# Palette_PCB.net
KiCad netlist of a schematic drawn in EAGLE
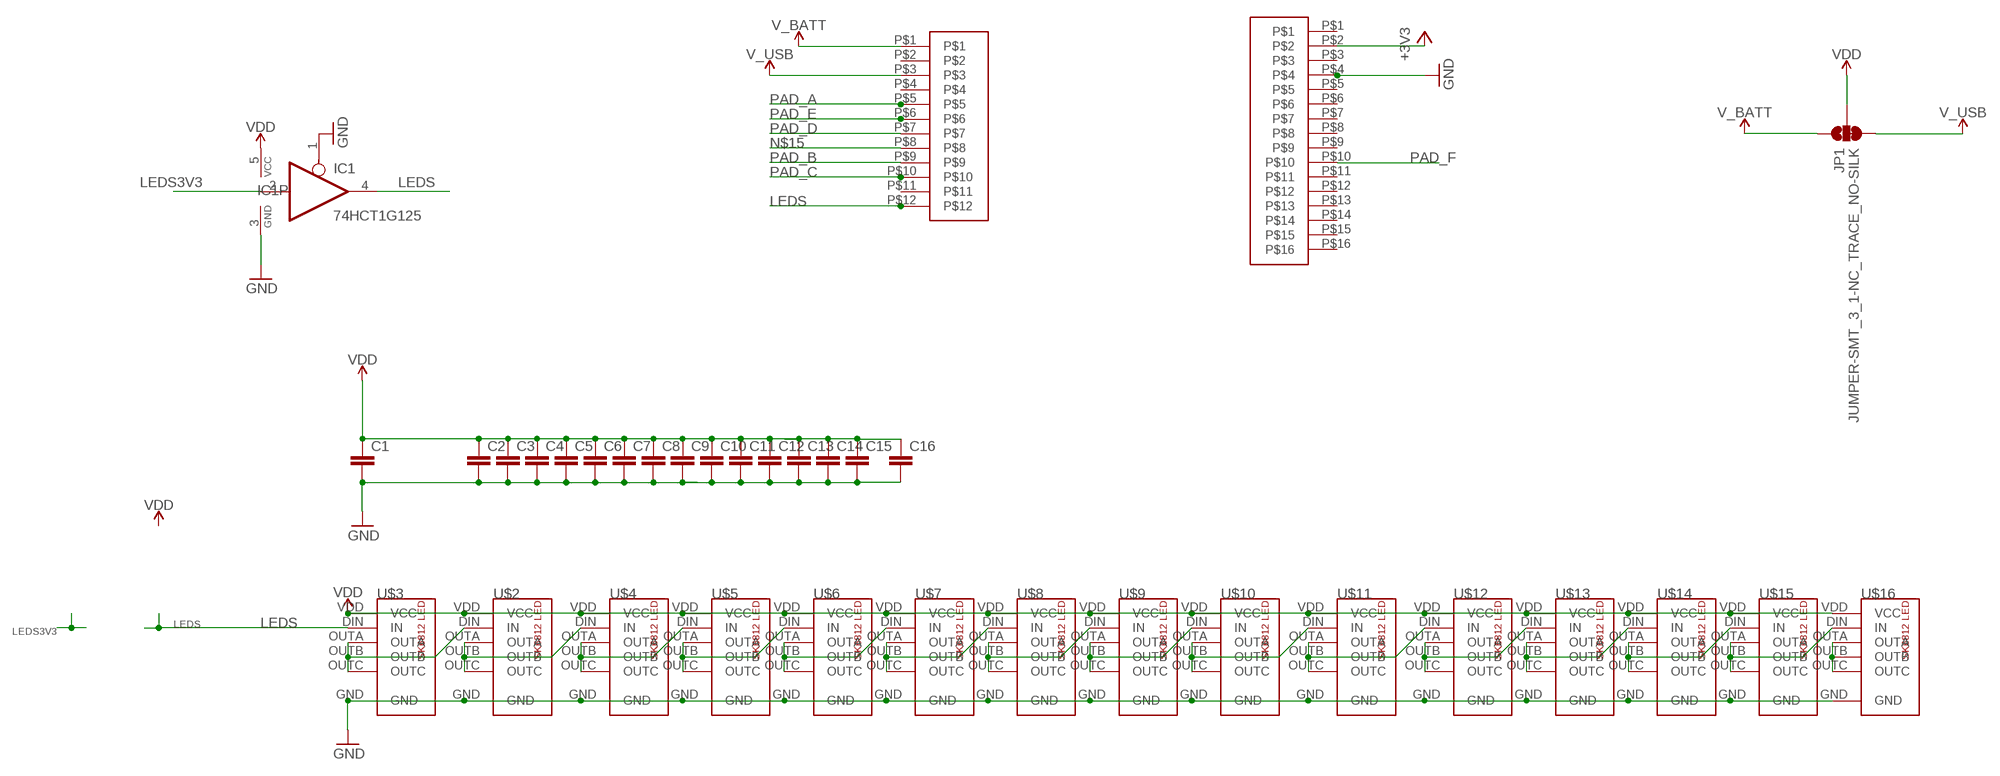
[diagram p0: schematic, sheet 1]

(export (version "E")
  (design (tool "Eeschema 10.0.6"))
  (components
    (comp (ref "C1")
      (value "C-EUC0402K")
      (footprint "eagle-import:C0402K")
      (libsource (lib "eagle-import") (part "C-EUC0402K"))
    )
    (comp (ref "C2")
      (value "C-EUC0402K")
      (footprint "eagle-import:C0402K")
      (libsource (lib "eagle-import") (part "C-EUC0402K"))
    )
    (comp (ref "C3")
      (value "C-EUC0402K")
      (footprint "eagle-import:C0402K")
      (libsource (lib "eagle-import") (part "C-EUC0402K"))
    )
    (comp (ref "C4")
      (value "C-EUC0402K")
      (footprint "eagle-import:C0402K")
      (libsource (lib "eagle-import") (part "C-EUC0402K"))
    )
    (comp (ref "C5")
      (value "C-EUC0402K")
      (footprint "eagle-import:C0402K")
      (libsource (lib "eagle-import") (part "C-EUC0402K"))
    )
    (comp (ref "C6")
      (value "C-EUC0402K")
      (footprint "eagle-import:C0402K")
      (libsource (lib "eagle-import") (part "C-EUC0402K"))
    )
    (comp (ref "C7")
      (value "C-EUC0402K")
      (footprint "eagle-import:C0402K")
      (libsource (lib "eagle-import") (part "C-EUC0402K"))
    )
    (comp (ref "C8")
      (value "C-EUC0402K")
      (footprint "eagle-import:C0402K")
      (libsource (lib "eagle-import") (part "C-EUC0402K"))
    )
    (comp (ref "C9")
      (value "C-EUC0402K")
      (footprint "eagle-import:C0402K")
      (libsource (lib "eagle-import") (part "C-EUC0402K"))
    )
    (comp (ref "C10")
      (value "C-EUC0402K")
      (footprint "eagle-import:C0402K")
      (libsource (lib "eagle-import") (part "C-EUC0402K"))
    )
    (comp (ref "C11")
      (value "C-EUC0402K")
      (footprint "eagle-import:C0402K")
      (libsource (lib "eagle-import") (part "C-EUC0402K"))
    )
    (comp (ref "C12")
      (value "C-EUC0402K")
      (footprint "eagle-import:C0402K")
      (libsource (lib "eagle-import") (part "C-EUC0402K"))
    )
    (comp (ref "C13")
      (value "C-EUC0402K")
      (footprint "eagle-import:C0402K")
      (libsource (lib "eagle-import") (part "C-EUC0402K"))
    )
    (comp (ref "C14")
      (value "C-EUC0402K")
      (footprint "eagle-import:C0402K")
      (libsource (lib "eagle-import") (part "C-EUC0402K"))
    )
    (comp (ref "C15")
      (value "C-EUC0402K")
      (footprint "eagle-import:C0402K")
      (libsource (lib "eagle-import") (part "C-EUC0402K"))
    )
    (comp (ref "C16")
      (value "C-EUC0805K")
      (footprint "eagle-import:C0805K")
      (libsource (lib "eagle-import") (part "C-EUC0805K"))
    )
    (comp (ref "IC1")
      (value "74HCT1G125")
      (footprint "eagle-import:SOT23-5")
      (libsource (lib "eagle-import") (part "741G125DBVAHC"))
    )
    (comp (ref "JP1")
      (value "JUMPER-SMT_3_1-NC_TRACE_NO-SILK")
      (footprint "eagle-import:SMT-JUMPER_3_1-NC_TRACE_NO-SILK")
      (libsource (lib "eagle-import") (part "JUMPER-SMT_3_1-NC_TRACE_NO-SILK"))
    )
    (comp (ref "U$2")
      (value "SK6812OK")
      (footprint "eagle-import:SK6812_V2C")
      (libsource (lib "eagle-import") (part "SK6812OK"))
    )
    (comp (ref "U$3")
      (value "SK6812OK")
      (footprint "eagle-import:SK6812_V2C")
      (libsource (lib "eagle-import") (part "SK6812OK"))
    )
    (comp (ref "U$4")
      (value "SK6812OK")
      (footprint "eagle-import:SK6812_V2C")
      (libsource (lib "eagle-import") (part "SK6812OK"))
    )
    (comp (ref "U$5")
      (value "SK6812OK")
      (footprint "eagle-import:SK6812_V2C")
      (libsource (lib "eagle-import") (part "SK6812OK"))
    )
    (comp (ref "U$6")
      (value "SK6812OK")
      (footprint "eagle-import:SK6812_V2C")
      (libsource (lib "eagle-import") (part "SK6812OK"))
    )
    (comp (ref "U$7")
      (value "SK6812OK")
      (footprint "eagle-import:SK6812_V2C")
      (libsource (lib "eagle-import") (part "SK6812OK"))
    )
    (comp (ref "U$8")
      (value "SK6812OK")
      (footprint "eagle-import:SK6812_V2C")
      (libsource (lib "eagle-import") (part "SK6812OK"))
    )
    (comp (ref "U$9")
      (value "SK6812OK")
      (footprint "eagle-import:SK6812_V2C")
      (libsource (lib "eagle-import") (part "SK6812OK"))
    )
    (comp (ref "U$10")
      (value "SK6812OK")
      (footprint "eagle-import:SK6812_V2C")
      (libsource (lib "eagle-import") (part "SK6812OK"))
    )
    (comp (ref "U$11")
      (value "SK6812OK")
      (footprint "eagle-import:SK6812_V2C")
      (libsource (lib "eagle-import") (part "SK6812OK"))
    )
    (comp (ref "U$12")
      (value "SK6812OK")
      (footprint "eagle-import:SK6812_V2C")
      (libsource (lib "eagle-import") (part "SK6812OK"))
    )
    (comp (ref "U$13")
      (value "SK6812OK")
      (footprint "eagle-import:SK6812_V2C")
      (libsource (lib "eagle-import") (part "SK6812OK"))
    )
    (comp (ref "U$14")
      (value "SK6812OK")
      (footprint "eagle-import:SK6812_V2C")
      (libsource (lib "eagle-import") (part "SK6812OK"))
    )
    (comp (ref "U$15")
      (value "SK6812OK")
      (footprint "eagle-import:SK6812_V2C")
      (libsource (lib "eagle-import") (part "SK6812OK"))
    )
    (comp (ref "U$16")
      (value "SK6812OK")
      (footprint "eagle-import:SK6812_V2C")
      (libsource (lib "eagle-import") (part "SK6812OK"))
    )
    (comp (ref "U$17")
      (value "SMD-FEMALE-HEADER-16")
      (footprint "eagle-import:SMD-FEMALE-HEADER-16")
      (libsource (lib "eagle-import") (part "SMD-FEMALE-HEADER-16"))
    )
    (comp (ref "U$18")
      (value "SMD-FEMALE-HEADER-12")
      (footprint "eagle-import:SMD-FEMALE-HEADER-12")
      (libsource (lib "eagle-import") (part "SMD-FEMALE-HEADER-12"))
    )
  )
  (nets
    (net (code "1") (name "+3V3") (class "Default")
      (node (ref "U$17") (pin "P$2") (pinfunction "P$2_P$2") (pintype "bidirectional"))
    )
    (net (code "2") (name "/N$15") (class "Default")
      (node (ref "U$18") (pin "P$8") (pinfunction "P$8_P$8") (pintype "bidirectional"))
    )
    (net (code "3") (name "/PAD_A") (class "Default")
      (node (ref "U$18") (pin "P$5") (pinfunction "P$5_P$5") (pintype "bidirectional"))
    )
    (net (code "4") (name "/PAD_B") (class "Default")
      (node (ref "U$18") (pin "P$9") (pinfunction "P$9_P$9") (pintype "bidirectional"))
    )
    (net (code "5") (name "/PAD_C") (class "Default")
      (node (ref "U$18") (pin "P$10") (pinfunction "P$10_P$10") (pintype "bidirectional"))
    )
    (net (code "6") (name "/PAD_D") (class "Default")
      (node (ref "U$18") (pin "P$7") (pinfunction "P$7_P$7") (pintype "bidirectional"))
    )
    (net (code "7") (name "/PAD_E") (class "Default")
      (node (ref "U$18") (pin "P$6") (pinfunction "P$6_P$6") (pintype "bidirectional"))
    )
    (net (code "8") (name "/PAD_F") (class "Default")
      (node (ref "U$17") (pin "P$10") (pinfunction "P$10_P$10") (pintype "bidirectional"))
    )
    (net (code "9") (name "GND") (class "Default")
      (node (ref "C1") (pin "2") (pinfunction "2_2") (pintype "passive"))
      (node (ref "C10") (pin "2") (pinfunction "2_2") (pintype "passive"))
      (node (ref "C11") (pin "2") (pinfunction "2_2") (pintype "passive"))
      (node (ref "C12") (pin "2") (pinfunction "2_2") (pintype "passive"))
      (node (ref "C13") (pin "2") (pinfunction "2_2") (pintype "passive"))
      (node (ref "C14") (pin "2") (pinfunction "2_2") (pintype "passive"))
      (node (ref "C15") (pin "2") (pinfunction "2_2") (pintype "passive"))
      (node (ref "C16") (pin "2") (pinfunction "2_2") (pintype "passive"))
      (node (ref "C2") (pin "2") (pinfunction "2_2") (pintype "passive"))
      (node (ref "C3") (pin "2") (pinfunction "2_2") (pintype "passive"))
      (node (ref "C4") (pin "2") (pinfunction "2_2") (pintype "passive"))
      (node (ref "C5") (pin "2") (pinfunction "2_2") (pintype "passive"))
      (node (ref "C6") (pin "2") (pinfunction "2_2") (pintype "passive"))
      (node (ref "C7") (pin "2") (pinfunction "2_2") (pintype "passive"))
      (node (ref "C8") (pin "2") (pinfunction "2_2") (pintype "passive"))
      (node (ref "C9") (pin "2") (pinfunction "2_2") (pintype "passive"))
      (node (ref "IC1") (pin "1") (pinfunction "OE_1") (pintype "input"))
      (node (ref "IC1") (pin "3") (pinfunction "GND_3") (pintype "power_in"))
      (node (ref "U$10") (pin "GND") (pinfunction "GND_GND") (pintype "bidirectional"))
      (node (ref "U$11") (pin "GND") (pinfunction "GND_GND") (pintype "bidirectional"))
      (node (ref "U$12") (pin "GND") (pinfunction "GND_GND") (pintype "bidirectional"))
      (node (ref "U$13") (pin "GND") (pinfunction "GND_GND") (pintype "bidirectional"))
      (node (ref "U$14") (pin "GND") (pinfunction "GND_GND") (pintype "bidirectional"))
      (node (ref "U$15") (pin "GND") (pinfunction "GND_GND") (pintype "bidirectional"))
      (node (ref "U$16") (pin "GND") (pinfunction "GND_GND") (pintype "bidirectional"))
      (node (ref "U$17") (pin "P$4") (pinfunction "P$4_P$4") (pintype "bidirectional"))
      (node (ref "U$2") (pin "GND") (pinfunction "GND_GND") (pintype "bidirectional"))
      (node (ref "U$3") (pin "GND") (pinfunction "GND_GND") (pintype "bidirectional"))
      (node (ref "U$4") (pin "GND") (pinfunction "GND_GND") (pintype "bidirectional"))
      (node (ref "U$5") (pin "GND") (pinfunction "GND_GND") (pintype "bidirectional"))
      (node (ref "U$6") (pin "GND") (pinfunction "GND_GND") (pintype "bidirectional"))
      (node (ref "U$7") (pin "GND") (pinfunction "GND_GND") (pintype "bidirectional"))
      (node (ref "U$8") (pin "GND") (pinfunction "GND_GND") (pintype "bidirectional"))
      (node (ref "U$9") (pin "GND") (pinfunction "GND_GND") (pintype "bidirectional"))
    )
    (net (code "10") (name "LEDS") (class "Default")
      (node (ref "IC1") (pin "4") (pinfunction "O_4") (pintype "tri_state"))
      (node (ref "U$18") (pin "P$12") (pinfunction "P$12_P$12") (pintype "bidirectional"))
      (node (ref "U$3") (pin "DIN") (pinfunction "IN_DIN") (pintype "bidirectional"))
    )
    (net (code "11") (name "LEDS3V3") (class "Default")
      (node (ref "IC1") (pin "2") (pinfunction "I_2") (pintype "input"))
    )
    (net (code "12") (name "Net-(U$2-IN)") (class "Default")
      (node (ref "U$2") (pin "DIN") (pinfunction "IN_DIN") (pintype "bidirectional"))
      (node (ref "U$3") (pin "OUTA") (pinfunction "OUTA_OUTA") (pintype "bidirectional"))
      (node (ref "U$3") (pin "OUTB") (pinfunction "OUTB_OUTB") (pintype "bidirectional"))
      (node (ref "U$3") (pin "OUTC") (pinfunction "OUTC_OUTC") (pintype "bidirectional"))
    )
    (net (code "13") (name "Net-(U$4-IN)") (class "Default")
      (node (ref "U$2") (pin "OUTA") (pinfunction "OUTA_OUTA") (pintype "bidirectional"))
      (node (ref "U$2") (pin "OUTB") (pinfunction "OUTB_OUTB") (pintype "bidirectional"))
      (node (ref "U$2") (pin "OUTC") (pinfunction "OUTC_OUTC") (pintype "bidirectional"))
      (node (ref "U$4") (pin "DIN") (pinfunction "IN_DIN") (pintype "bidirectional"))
    )
    (net (code "14") (name "Net-(U$5-IN)") (class "Default")
      (node (ref "U$4") (pin "OUTA") (pinfunction "OUTA_OUTA") (pintype "bidirectional"))
      (node (ref "U$4") (pin "OUTB") (pinfunction "OUTB_OUTB") (pintype "bidirectional"))
      (node (ref "U$4") (pin "OUTC") (pinfunction "OUTC_OUTC") (pintype "bidirectional"))
      (node (ref "U$5") (pin "DIN") (pinfunction "IN_DIN") (pintype "bidirectional"))
    )
    (net (code "15") (name "Net-(U$6-IN)") (class "Default")
      (node (ref "U$5") (pin "OUTA") (pinfunction "OUTA_OUTA") (pintype "bidirectional"))
      (node (ref "U$5") (pin "OUTB") (pinfunction "OUTB_OUTB") (pintype "bidirectional"))
      (node (ref "U$5") (pin "OUTC") (pinfunction "OUTC_OUTC") (pintype "bidirectional"))
      (node (ref "U$6") (pin "DIN") (pinfunction "IN_DIN") (pintype "bidirectional"))
    )
    (net (code "16") (name "Net-(U$7-IN)") (class "Default")
      (node (ref "U$6") (pin "OUTA") (pinfunction "OUTA_OUTA") (pintype "bidirectional"))
      (node (ref "U$6") (pin "OUTB") (pinfunction "OUTB_OUTB") (pintype "bidirectional"))
      (node (ref "U$6") (pin "OUTC") (pinfunction "OUTC_OUTC") (pintype "bidirectional"))
      (node (ref "U$7") (pin "DIN") (pinfunction "IN_DIN") (pintype "bidirectional"))
    )
    (net (code "17") (name "Net-(U$8-IN)") (class "Default")
      (node (ref "U$7") (pin "OUTA") (pinfunction "OUTA_OUTA") (pintype "bidirectional"))
      (node (ref "U$7") (pin "OUTB") (pinfunction "OUTB_OUTB") (pintype "bidirectional"))
      (node (ref "U$7") (pin "OUTC") (pinfunction "OUTC_OUTC") (pintype "bidirectional"))
      (node (ref "U$8") (pin "DIN") (pinfunction "IN_DIN") (pintype "bidirectional"))
    )
    (net (code "18") (name "Net-(U$9-IN)") (class "Default")
      (node (ref "U$8") (pin "OUTA") (pinfunction "OUTA_OUTA") (pintype "bidirectional"))
      (node (ref "U$8") (pin "OUTB") (pinfunction "OUTB_OUTB") (pintype "bidirectional"))
      (node (ref "U$8") (pin "OUTC") (pinfunction "OUTC_OUTC") (pintype "bidirectional"))
      (node (ref "U$9") (pin "DIN") (pinfunction "IN_DIN") (pintype "bidirectional"))
    )
    (net (code "19") (name "Net-(U$10-IN)") (class "Default")
      (node (ref "U$10") (pin "DIN") (pinfunction "IN_DIN") (pintype "bidirectional"))
      (node (ref "U$9") (pin "OUTA") (pinfunction "OUTA_OUTA") (pintype "bidirectional"))
      (node (ref "U$9") (pin "OUTB") (pinfunction "OUTB_OUTB") (pintype "bidirectional"))
      (node (ref "U$9") (pin "OUTC") (pinfunction "OUTC_OUTC") (pintype "bidirectional"))
    )
    (net (code "20") (name "Net-(U$11-IN)") (class "Default")
      (node (ref "U$10") (pin "OUTA") (pinfunction "OUTA_OUTA") (pintype "bidirectional"))
      (node (ref "U$10") (pin "OUTB") (pinfunction "OUTB_OUTB") (pintype "bidirectional"))
      (node (ref "U$10") (pin "OUTC") (pinfunction "OUTC_OUTC") (pintype "bidirectional"))
      (node (ref "U$11") (pin "DIN") (pinfunction "IN_DIN") (pintype "bidirectional"))
    )
    (net (code "21") (name "Net-(U$12-IN)") (class "Default")
      (node (ref "U$11") (pin "OUTA") (pinfunction "OUTA_OUTA") (pintype "bidirectional"))
      (node (ref "U$11") (pin "OUTB") (pinfunction "OUTB_OUTB") (pintype "bidirectional"))
      (node (ref "U$11") (pin "OUTC") (pinfunction "OUTC_OUTC") (pintype "bidirectional"))
      (node (ref "U$12") (pin "DIN") (pinfunction "IN_DIN") (pintype "bidirectional"))
    )
    (net (code "22") (name "Net-(U$13-IN)") (class "Default")
      (node (ref "U$12") (pin "OUTA") (pinfunction "OUTA_OUTA") (pintype "bidirectional"))
      (node (ref "U$12") (pin "OUTB") (pinfunction "OUTB_OUTB") (pintype "bidirectional"))
      (node (ref "U$12") (pin "OUTC") (pinfunction "OUTC_OUTC") (pintype "bidirectional"))
      (node (ref "U$13") (pin "DIN") (pinfunction "IN_DIN") (pintype "bidirectional"))
    )
    (net (code "23") (name "Net-(U$14-IN)") (class "Default")
      (node (ref "U$13") (pin "OUTA") (pinfunction "OUTA_OUTA") (pintype "bidirectional"))
      (node (ref "U$13") (pin "OUTB") (pinfunction "OUTB_OUTB") (pintype "bidirectional"))
      (node (ref "U$13") (pin "OUTC") (pinfunction "OUTC_OUTC") (pintype "bidirectional"))
      (node (ref "U$14") (pin "DIN") (pinfunction "IN_DIN") (pintype "bidirectional"))
    )
    (net (code "24") (name "Net-(U$15-IN)") (class "Default")
      (node (ref "U$14") (pin "OUTA") (pinfunction "OUTA_OUTA") (pintype "bidirectional"))
      (node (ref "U$14") (pin "OUTB") (pinfunction "OUTB_OUTB") (pintype "bidirectional"))
      (node (ref "U$14") (pin "OUTC") (pinfunction "OUTC_OUTC") (pintype "bidirectional"))
      (node (ref "U$15") (pin "DIN") (pinfunction "IN_DIN") (pintype "bidirectional"))
    )
    (net (code "25") (name "Net-(U$16-IN)") (class "Default")
      (node (ref "U$15") (pin "OUTA") (pinfunction "OUTA_OUTA") (pintype "bidirectional"))
      (node (ref "U$15") (pin "OUTB") (pinfunction "OUTB_OUTB") (pintype "bidirectional"))
      (node (ref "U$15") (pin "OUTC") (pinfunction "OUTC_OUTC") (pintype "bidirectional"))
      (node (ref "U$16") (pin "DIN") (pinfunction "IN_DIN") (pintype "bidirectional"))
    )
    (net (code "26") (name "Net-(U$16-PadOUTA)") (class "Default")
      (node (ref "U$16") (pin "OUTA") (pinfunction "OUTA_OUTA") (pintype "bidirectional"))
      (node (ref "U$16") (pin "OUTB") (pinfunction "OUTB_OUTB") (pintype "bidirectional"))
      (node (ref "U$16") (pin "OUTC") (pinfunction "OUTC_OUTC") (pintype "bidirectional"))
    )
    (net (code "27") (name "VDD") (class "Default")
      (node (ref "C1") (pin "1") (pinfunction "1_1") (pintype "passive"))
      (node (ref "C10") (pin "1") (pinfunction "1_1") (pintype "passive"))
      (node (ref "C11") (pin "1") (pinfunction "1_1") (pintype "passive"))
      (node (ref "C12") (pin "1") (pinfunction "1_1") (pintype "passive"))
      (node (ref "C13") (pin "1") (pinfunction "1_1") (pintype "passive"))
      (node (ref "C14") (pin "1") (pinfunction "1_1") (pintype "passive"))
      (node (ref "C15") (pin "1") (pinfunction "1_1") (pintype "passive"))
      (node (ref "C16") (pin "1") (pinfunction "1_1") (pintype "passive"))
      (node (ref "C2") (pin "1") (pinfunction "1_1") (pintype "passive"))
      (node (ref "C3") (pin "1") (pinfunction "1_1") (pintype "passive"))
      (node (ref "C4") (pin "1") (pinfunction "1_1") (pintype "passive"))
      (node (ref "C5") (pin "1") (pinfunction "1_1") (pintype "passive"))
      (node (ref "C6") (pin "1") (pinfunction "1_1") (pintype "passive"))
      (node (ref "C7") (pin "1") (pinfunction "1_1") (pintype "passive"))
      (node (ref "C8") (pin "1") (pinfunction "1_1") (pintype "passive"))
      (node (ref "C9") (pin "1") (pinfunction "1_1") (pintype "passive"))
      (node (ref "IC1") (pin "5") (pinfunction "VCC_5") (pintype "power_in"))
      (node (ref "JP1") (pin "2") (pinfunction "2_2") (pintype "passive"))
      (node (ref "U$10") (pin "VDD") (pinfunction "VCC_VDD") (pintype "bidirectional"))
      (node (ref "U$11") (pin "VDD") (pinfunction "VCC_VDD") (pintype "bidirectional"))
      (node (ref "U$12") (pin "VDD") (pinfunction "VCC_VDD") (pintype "bidirectional"))
      (node (ref "U$13") (pin "VDD") (pinfunction "VCC_VDD") (pintype "bidirectional"))
      (node (ref "U$14") (pin "VDD") (pinfunction "VCC_VDD") (pintype "bidirectional"))
      (node (ref "U$15") (pin "VDD") (pinfunction "VCC_VDD") (pintype "bidirectional"))
      (node (ref "U$16") (pin "VDD") (pinfunction "VCC_VDD") (pintype "bidirectional"))
      (node (ref "U$2") (pin "VDD") (pinfunction "VCC_VDD") (pintype "bidirectional"))
      (node (ref "U$3") (pin "VDD") (pinfunction "VCC_VDD") (pintype "bidirectional"))
      (node (ref "U$4") (pin "VDD") (pinfunction "VCC_VDD") (pintype "bidirectional"))
      (node (ref "U$5") (pin "VDD") (pinfunction "VCC_VDD") (pintype "bidirectional"))
      (node (ref "U$6") (pin "VDD") (pinfunction "VCC_VDD") (pintype "bidirectional"))
      (node (ref "U$7") (pin "VDD") (pinfunction "VCC_VDD") (pintype "bidirectional"))
      (node (ref "U$8") (pin "VDD") (pinfunction "VCC_VDD") (pintype "bidirectional"))
      (node (ref "U$9") (pin "VDD") (pinfunction "VCC_VDD") (pintype "bidirectional"))
    )
    (net (code "28") (name "V_BATT") (class "Default")
      (node (ref "JP1") (pin "1") (pinfunction "1_1") (pintype "passive"))
      (node (ref "U$18") (pin "P$1") (pinfunction "P$1_P$1") (pintype "bidirectional"))
    )
    (net (code "29") (name "V_USB") (class "Default")
      (node (ref "JP1") (pin "3") (pinfunction "3_3") (pintype "passive"))
      (node (ref "U$18") (pin "P$3") (pinfunction "P$3_P$3") (pintype "bidirectional"))
    )
    (net (code "30") (name "unconnected-(U$17-PadP$1)") (class "Default")
      (node (ref "U$17") (pin "P$1") (pinfunction "P$1_P$1") (pintype "bidirectional"))
    )
    (net (code "31") (name "unconnected-(U$17-PadP$3)") (class "Default")
      (node (ref "U$17") (pin "P$3") (pinfunction "P$3_P$3") (pintype "bidirectional"))
    )
    (net (code "32") (name "unconnected-(U$17-PadP$5)") (class "Default")
      (node (ref "U$17") (pin "P$5") (pinfunction "P$5_P$5") (pintype "bidirectional"))
    )
    (net (code "33") (name "unconnected-(U$17-PadP$6)") (class "Default")
      (node (ref "U$17") (pin "P$6") (pinfunction "P$6_P$6") (pintype "bidirectional"))
    )
    (net (code "34") (name "unconnected-(U$17-PadP$7)") (class "Default")
      (node (ref "U$17") (pin "P$7") (pinfunction "P$7_P$7") (pintype "bidirectional"))
    )
    (net (code "35") (name "unconnected-(U$17-PadP$8)") (class "Default")
      (node (ref "U$17") (pin "P$8") (pinfunction "P$8_P$8") (pintype "bidirectional"))
    )
    (net (code "36") (name "unconnected-(U$17-PadP$9)") (class "Default")
      (node (ref "U$17") (pin "P$9") (pinfunction "P$9_P$9") (pintype "bidirectional"))
    )
    (net (code "37") (name "unconnected-(U$17-PadP$11)") (class "Default")
      (node (ref "U$17") (pin "P$11") (pinfunction "P$11_P$11") (pintype "bidirectional"))
    )
    (net (code "38") (name "unconnected-(U$17-PadP$12)") (class "Default")
      (node (ref "U$17") (pin "P$12") (pinfunction "P$12_P$12") (pintype "bidirectional"))
    )
    (net (code "39") (name "unconnected-(U$17-PadP$13)") (class "Default")
      (node (ref "U$17") (pin "P$13") (pinfunction "P$13_P$13") (pintype "bidirectional"))
    )
    (net (code "40") (name "unconnected-(U$17-PadP$14)") (class "Default")
      (node (ref "U$17") (pin "P$14") (pinfunction "P$14_P$14") (pintype "bidirectional"))
    )
    (net (code "41") (name "unconnected-(U$17-PadP$15)") (class "Default")
      (node (ref "U$17") (pin "P$15") (pinfunction "P$15_P$15") (pintype "bidirectional"))
    )
    (net (code "42") (name "unconnected-(U$17-PadP$16)") (class "Default")
      (node (ref "U$17") (pin "P$16") (pinfunction "P$16_P$16") (pintype "bidirectional"))
    )
    (net (code "43") (name "unconnected-(U$18-PadP$2)") (class "Default")
      (node (ref "U$18") (pin "P$2") (pinfunction "P$2_P$2") (pintype "bidirectional"))
    )
    (net (code "44") (name "unconnected-(U$18-PadP$4)") (class "Default")
      (node (ref "U$18") (pin "P$4") (pinfunction "P$4_P$4") (pintype "bidirectional"))
    )
    (net (code "45") (name "unconnected-(U$18-PadP$11)") (class "Default")
      (node (ref "U$18") (pin "P$11") (pinfunction "P$11_P$11") (pintype "bidirectional"))
    )
  )
)
